# Headers.net
KiCad netlist of a schematic drawn in EAGLE
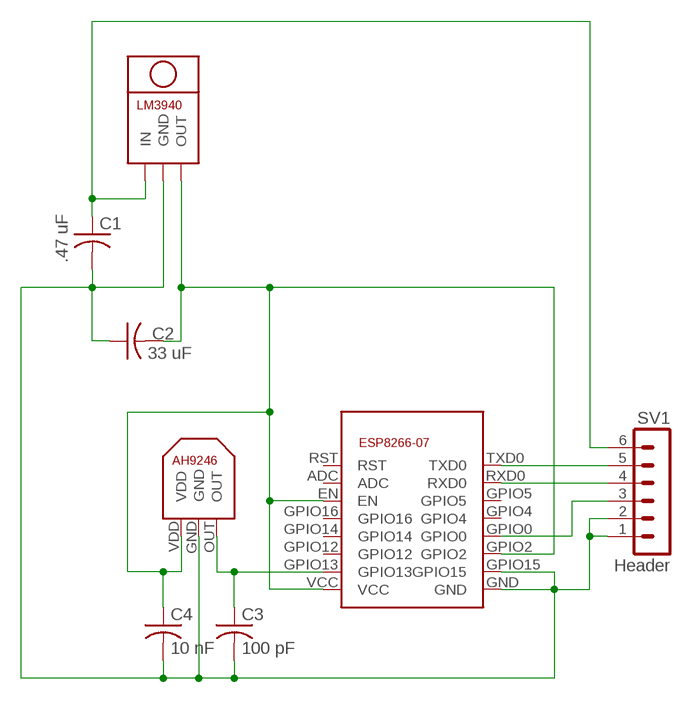
[diagram p0: schematic, sheet 1]

(export (version "E")
  (design (tool "Eeschema 10.0.6"))
  (components
    (comp (ref "C1")
      (value ".47 uF")
      (footprint "eagle-import:C025-050X050")
      (libsource (lib "eagle-import") (part "C-US025-050X050"))
    )
    (comp (ref "C2")
      (value "33 uF")
      (footprint "eagle-import:C025-050X050")
      (libsource (lib "eagle-import") (part "C-US025-050X050"))
    )
    (comp (ref "C3")
      (value "100 pF")
      (footprint "eagle-import:C025-050X050")
      (libsource (lib "eagle-import") (part "C-US025-050X050"))
    )
    (comp (ref "C4")
      (value "10 nF")
      (footprint "eagle-import:C025-050X050")
      (libsource (lib "eagle-import") (part "C-US025-050X050"))
    )
    (comp (ref "SV1")
      (value "Header")
      (footprint "eagle-import:MA06-1")
      (libsource (lib "eagle-import") (part "MA06-1"))
    )
    (comp (ref "U$1")
      (value "ESP8266-07")
      (footprint "eagle-import:ESP8266-07")
      (libsource (lib "eagle-import") (part "ESP8266-07"))
    )
    (comp (ref "U$2")
      (value "LM3940")
      (footprint "eagle-import:LM3940")
      (libsource (lib "eagle-import") (part "LM3940"))
    )
    (comp (ref "U$3")
      (value "AH9246")
      (footprint "eagle-import:AH9246")
      (libsource (lib "eagle-import") (part "AH9246"))
    )
  )
  (nets
    (net (code "1") (name "Net-(C1-Pad1)") (class "Default")
      (node (ref "C1") (pin "1") (pinfunction "1_1") (pintype "passive"))
      (node (ref "SV1") (pin "6") (pinfunction "6_6") (pintype "passive"))
      (node (ref "U$2") (pin "IN") (pinfunction "IN_IN") (pintype "input"))
    )
    (net (code "2") (name "Net-(C1-Pad2)") (class "Default")
      (node (ref "C1") (pin "2") (pinfunction "2_2") (pintype "passive"))
      (node (ref "C2") (pin "1") (pinfunction "1_1") (pintype "passive"))
      (node (ref "C3") (pin "2") (pinfunction "2_2") (pintype "passive"))
      (node (ref "C4") (pin "2") (pinfunction "2_2") (pintype "passive"))
      (node (ref "SV1") (pin "1") (pinfunction "1_1") (pintype "passive"))
      (node (ref "SV1") (pin "2") (pinfunction "2_2") (pintype "passive"))
      (node (ref "U$1") (pin "GND") (pinfunction "GND_GND") (pintype "power_in"))
      (node (ref "U$1") (pin "GPIO15") (pinfunction "GPIO15_GPIO15") (pintype "bidirectional"))
      (node (ref "U$2") (pin "GND") (pinfunction "GND_GND") (pintype "power_in"))
      (node (ref "U$3") (pin "GND") (pinfunction "GND_GND") (pintype "power_in"))
    )
    (net (code "3") (name "Net-(C2-Pad2)") (class "Default")
      (node (ref "C2") (pin "2") (pinfunction "2_2") (pintype "passive"))
      (node (ref "C4") (pin "1") (pinfunction "1_1") (pintype "passive"))
      (node (ref "U$1") (pin "EN") (pinfunction "EN_EN") (pintype "input"))
      (node (ref "U$1") (pin "GPIO2") (pinfunction "GPIO2_GPIO2") (pintype "bidirectional"))
      (node (ref "U$1") (pin "VCC") (pinfunction "VCC_VCC") (pintype "power_in"))
      (node (ref "U$2") (pin "OUT") (pinfunction "OUT_OUT") (pintype "output"))
      (node (ref "U$3") (pin "VDD") (pinfunction "VDD_VDD") (pintype "power_in"))
    )
    (net (code "4") (name "Net-(C3-Pad1)") (class "Default")
      (node (ref "C3") (pin "1") (pinfunction "1_1") (pintype "passive"))
      (node (ref "U$1") (pin "GPIO13") (pinfunction "GPIO13_GPIO13") (pintype "bidirectional"))
      (node (ref "U$3") (pin "OUT") (pinfunction "OUT_OUT") (pintype "output"))
    )
    (net (code "5") (name "Net-(SV1-Pad3)") (class "Default")
      (node (ref "SV1") (pin "3") (pinfunction "3_3") (pintype "passive"))
      (node (ref "U$1") (pin "GPIO0") (pinfunction "GPIO0_GPIO0") (pintype "bidirectional"))
    )
    (net (code "6") (name "Net-(SV1-Pad4)") (class "Default")
      (node (ref "SV1") (pin "4") (pinfunction "4_4") (pintype "passive"))
      (node (ref "U$1") (pin "RXD0") (pinfunction "RXD0_RXD0") (pintype "bidirectional"))
    )
    (net (code "7") (name "Net-(SV1-Pad5)") (class "Default")
      (node (ref "SV1") (pin "5") (pinfunction "5_5") (pintype "passive"))
      (node (ref "U$1") (pin "TXD0") (pinfunction "TXD0_TXD0") (pintype "bidirectional"))
    )
    (net (code "8") (name "unconnected-(U$1-PadADC)") (class "Default")
      (node (ref "U$1") (pin "ADC") (pinfunction "ADC_ADC") (pintype "input"))
    )
    (net (code "9") (name "unconnected-(U$1-PadGPIO4)") (class "Default")
      (node (ref "U$1") (pin "GPIO4") (pinfunction "GPIO4_GPIO4") (pintype "bidirectional"))
    )
    (net (code "10") (name "unconnected-(U$1-PadGPIO5)") (class "Default")
      (node (ref "U$1") (pin "GPIO5") (pinfunction "GPIO5_GPIO5") (pintype "bidirectional"))
    )
    (net (code "11") (name "unconnected-(U$1-PadGPIO12)") (class "Default")
      (node (ref "U$1") (pin "GPIO12") (pinfunction "GPIO12_GPIO12") (pintype "bidirectional"))
    )
    (net (code "12") (name "unconnected-(U$1-PadGPIO14)") (class "Default")
      (node (ref "U$1") (pin "GPIO14") (pinfunction "GPIO14_GPIO14") (pintype "bidirectional"))
    )
    (net (code "13") (name "unconnected-(U$1-PadGPIO16)") (class "Default")
      (node (ref "U$1") (pin "GPIO16") (pinfunction "GPIO16_GPIO16") (pintype "bidirectional"))
    )
    (net (code "14") (name "unconnected-(U$1-PadRST)") (class "Default")
      (node (ref "U$1") (pin "RST") (pinfunction "RST_RST") (pintype "input"))
    )
  )
)
